# atari2600.net
KiCad netlist of a schematic drawn in EAGLE
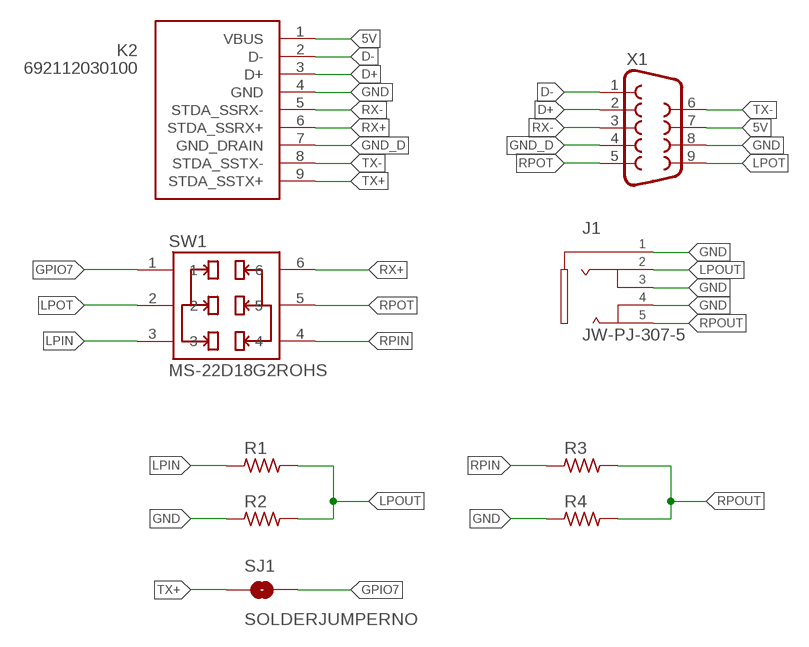
[diagram p0: schematic, sheet 1]

(export (version "E")
  (design (tool "Eeschema 10.0.6"))
  (components
    (comp (ref "J1")
      (value "JW-PJ-307-5")
      (footprint "eagle-import:JW-PJ-307-X")
      (libsource (lib "eagle-import") (part "JW-PJ-307-5"))
    )
    (comp (ref "K2")
      (value "692112030100")
      (footprint "eagle-import:692112030100")
      (libsource (lib "eagle-import") (part "692112030100"))
    )
    (comp (ref "R1")
      (value "R_0603")
      (footprint "eagle-import:R0603")
      (libsource (lib "eagle-import") (part "R_0603"))
    )
    (comp (ref "R2")
      (value "R_0603")
      (footprint "eagle-import:R0603")
      (libsource (lib "eagle-import") (part "R_0603"))
    )
    (comp (ref "R3")
      (value "R_0603")
      (footprint "eagle-import:R0603")
      (libsource (lib "eagle-import") (part "R_0603"))
    )
    (comp (ref "R4")
      (value "R_0603")
      (footprint "eagle-import:R0603")
      (libsource (lib "eagle-import") (part "R_0603"))
    )
    (comp (ref "SJ1")
      (value "SOLDERJUMPERNO")
      (footprint "eagle-import:SJ_2S-NO")
      (libsource (lib "eagle-import") (part "SOLDERJUMPERNO"))
    )
    (comp (ref "SW1")
      (value "MS-22D18G2ROHS")
      (footprint "eagle-import:SW_MS-22D18G2ROHS")
      (fields (field (name "MF") "Deyilong") (field (name "MP") "MS-22D18 G2 ROHS"))
      (libsource (lib "eagle-import") (part "MS-22D18G2ROHS"))
    )
    (comp (ref "X1")
      (value "DB9MALE")
      (footprint "eagle-import:DB9_MALE")
      (libsource (lib "eagle-import") (part "DB9MALE"))
    )
  )
  (nets
    (net (code "1") (name "5V") (class "Default")
      (node (ref "K2") (pin "1") (pinfunction "VBUS_1") (pintype "bidirectional"))
      (node (ref "X1") (pin "7") (pinfunction "7_7") (pintype "passive"))
    )
    (net (code "2") (name "D+") (class "Default")
      (node (ref "K2") (pin "3") (pinfunction "D+_3") (pintype "bidirectional"))
      (node (ref "X1") (pin "2") (pinfunction "2_2") (pintype "passive"))
    )
    (net (code "3") (name "D-") (class "Default")
      (node (ref "K2") (pin "2") (pinfunction "D-_2") (pintype "bidirectional"))
      (node (ref "X1") (pin "1") (pinfunction "1_1") (pintype "passive"))
    )
    (net (code "4") (name "GND") (class "Default")
      (node (ref "J1") (pin "P$1") (pinfunction "1_P$1") (pintype "passive"))
      (node (ref "J1") (pin "P$3") (pinfunction "3_P$3") (pintype "passive"))
      (node (ref "J1") (pin "P$4") (pinfunction "4_P$4") (pintype "passive"))
      (node (ref "K2") (pin "4") (pinfunction "GND_4") (pintype "bidirectional"))
      (node (ref "R2") (pin "1") (pinfunction "1_1") (pintype "passive"))
      (node (ref "R4") (pin "1") (pinfunction "1_1") (pintype "passive"))
      (node (ref "X1") (pin "8") (pinfunction "8_8") (pintype "passive"))
    )
    (net (code "5") (name "GND_D") (class "Default")
      (node (ref "K2") (pin "7") (pinfunction "GND_DRAIN_7") (pintype "bidirectional"))
      (node (ref "X1") (pin "4") (pinfunction "4_4") (pintype "passive"))
    )
    (net (code "6") (name "GPIO7") (class "Default")
      (node (ref "SJ1") (pin "2") (pinfunction "2_2") (pintype "passive"))
      (node (ref "SW1") (pin "1") (pinfunction "1_1") (pintype "passive"))
    )
    (net (code "7") (name "LPIN") (class "Default")
      (node (ref "R1") (pin "1") (pinfunction "1_1") (pintype "passive"))
      (node (ref "SW1") (pin "3") (pinfunction "3_3") (pintype "passive"))
    )
    (net (code "8") (name "LPOT") (class "Default")
      (node (ref "SW1") (pin "2") (pinfunction "2_2") (pintype "passive"))
      (node (ref "X1") (pin "9") (pinfunction "9_9") (pintype "passive"))
    )
    (net (code "9") (name "LPOUT") (class "Default")
      (node (ref "J1") (pin "P$2") (pinfunction "2_P$2") (pintype "passive"))
      (node (ref "R1") (pin "2") (pinfunction "2_2") (pintype "passive"))
      (node (ref "R2") (pin "2") (pinfunction "2_2") (pintype "passive"))
    )
    (net (code "10") (name "RPIN") (class "Default")
      (node (ref "R3") (pin "1") (pinfunction "1_1") (pintype "passive"))
      (node (ref "SW1") (pin "4") (pinfunction "4_4") (pintype "passive"))
    )
    (net (code "11") (name "RPOT") (class "Default")
      (node (ref "SW1") (pin "5") (pinfunction "5_5") (pintype "passive"))
      (node (ref "X1") (pin "5") (pinfunction "5_5") (pintype "passive"))
    )
    (net (code "12") (name "RPOUT") (class "Default")
      (node (ref "J1") (pin "P$5") (pinfunction "5_P$5") (pintype "passive"))
      (node (ref "R3") (pin "2") (pinfunction "2_2") (pintype "passive"))
      (node (ref "R4") (pin "2") (pinfunction "2_2") (pintype "passive"))
    )
    (net (code "13") (name "RX+") (class "Default")
      (node (ref "K2") (pin "6") (pinfunction "STDA_SSRX+_6") (pintype "bidirectional"))
      (node (ref "SW1") (pin "6") (pinfunction "6_6") (pintype "passive"))
    )
    (net (code "14") (name "RX-") (class "Default")
      (node (ref "K2") (pin "5") (pinfunction "STDA_SSRX-_5") (pintype "bidirectional"))
      (node (ref "X1") (pin "3") (pinfunction "3_3") (pintype "passive"))
    )
    (net (code "15") (name "TX+") (class "Default")
      (node (ref "K2") (pin "9") (pinfunction "STDA_SSTX+_9") (pintype "bidirectional"))
      (node (ref "SJ1") (pin "1") (pinfunction "1_1") (pintype "passive"))
    )
    (net (code "16") (name "TX-") (class "Default")
      (node (ref "K2") (pin "8") (pinfunction "STDA_SSTX-_8") (pintype "bidirectional"))
      (node (ref "X1") (pin "6") (pinfunction "6_6") (pintype "passive"))
    )
  )
)
